# Pg1_Microcontroller.net
KiCad netlist of a schematic drawn in Altium Designer
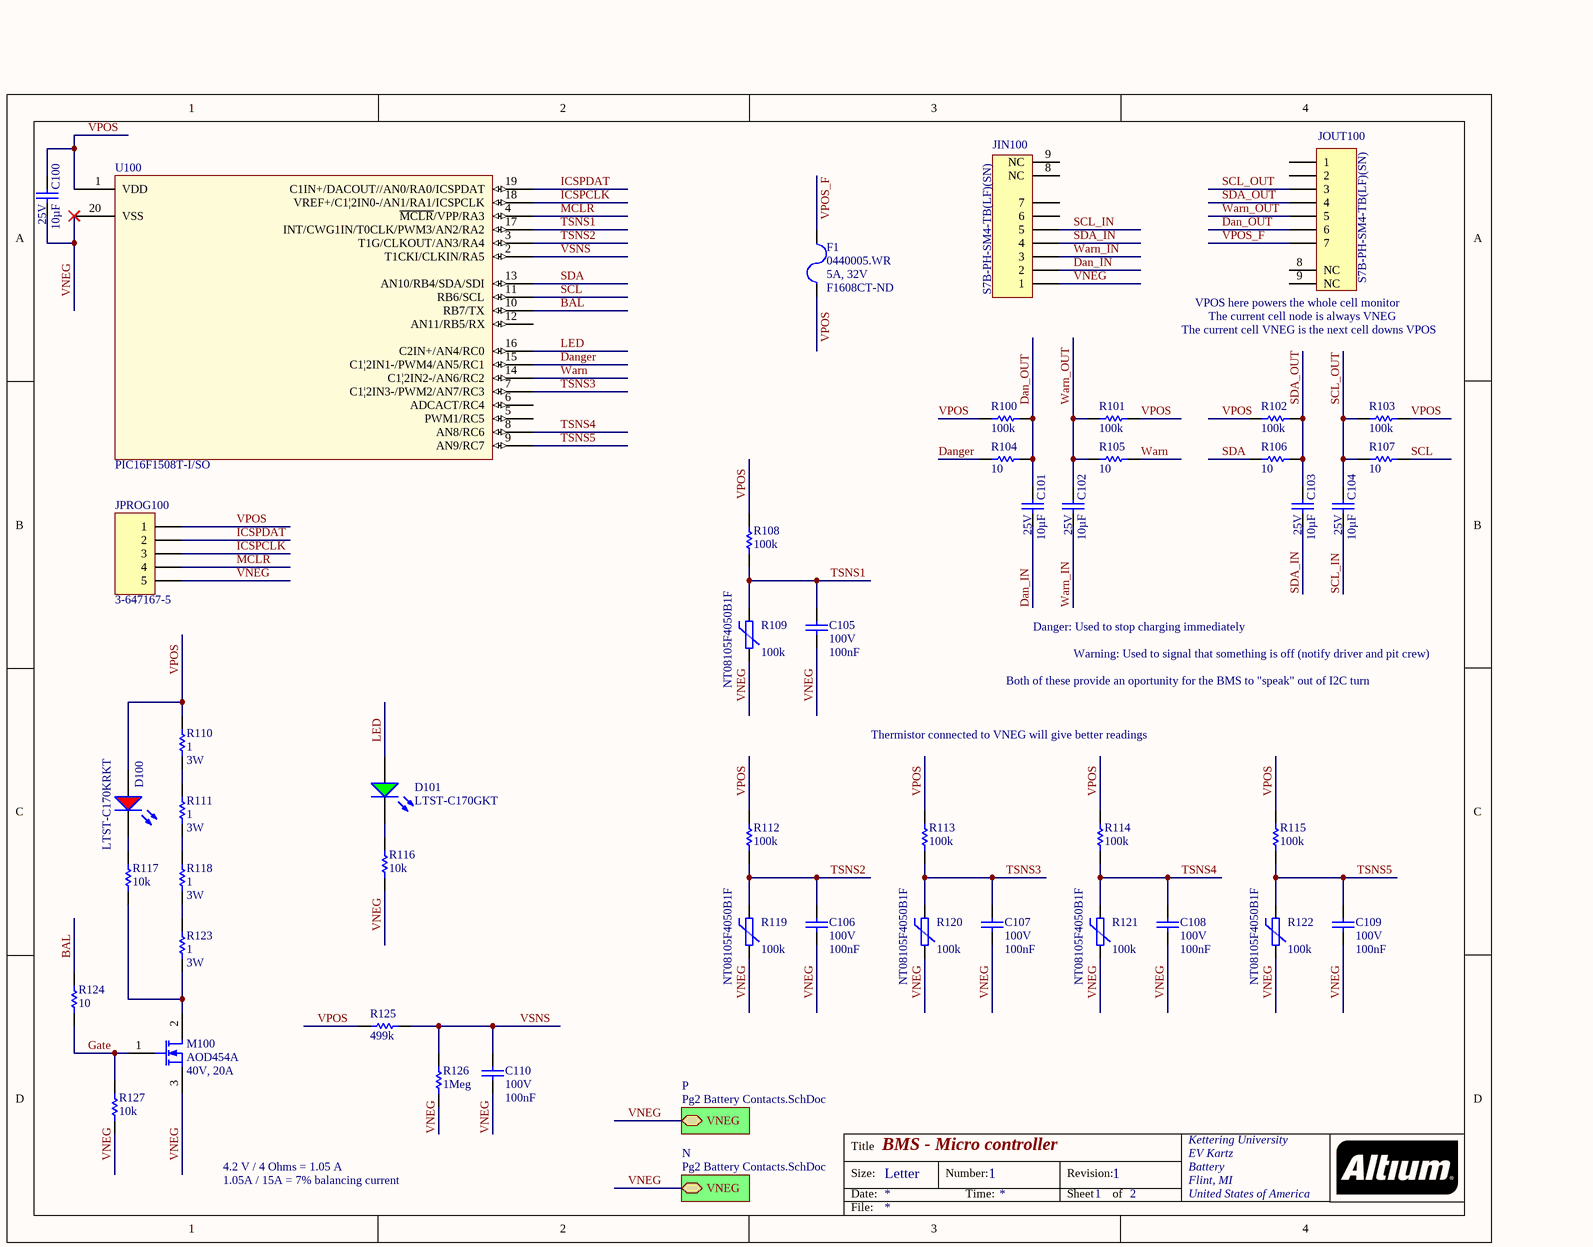
[diagram p0: Pg1 Microcontroller.SchDoc]

(export (version "E")
  (design (tool "Eeschema 10.0.6"))
  (components
    (comp (ref "C100")
      (value "10µF")
      (footprint "CAPC3225N")
      (description "Capacitor, Ceramic, 10µF, 25V, 0805, 10%, 125C")
      (fields (field (name "RATED") "25V") (field (name "Comment") "C1210C106K3RACAUTO"))
      (libsource (lib "SchLib - EE391 Master") (part "C1210C106K3RACAUTO"))
    )
    (comp (ref "C101")
      (value "10µF")
      (footprint "CAPC3225N")
      (description "Capacitor, Ceramic, 10µF, 25V, 0805, 10%, 125C")
      (fields (field (name "RATED") "25V") (field (name "Comment") "C1210C106K3RACAUTO"))
      (libsource (lib "SchLib - EE391 Master") (part "C1210C106K3RACAUTO"))
    )
    (comp (ref "C102")
      (value "10µF")
      (footprint "CAPC3225N")
      (description "Capacitor, Ceramic, 10µF, 25V, 0805, 10%, 125C")
      (fields (field (name "RATED") "25V") (field (name "Comment") "C1210C106K3RACAUTO"))
      (libsource (lib "SchLib - EE391 Master") (part "C1210C106K3RACAUTO"))
    )
    (comp (ref "C103")
      (value "10µF")
      (footprint "CAPC3225N")
      (description "Capacitor, Ceramic, 10µF, 25V, 0805, 10%, 125C")
      (fields (field (name "RATED") "25V") (field (name "Comment") "C1210C106K3RACAUTO"))
      (libsource (lib "SchLib - EE391 Master") (part "C1210C106K3RACAUTO"))
    )
    (comp (ref "C104")
      (value "10µF")
      (footprint "CAPC3225N")
      (description "Capacitor, Ceramic, 10µF, 25V, 0805, 10%, 125C")
      (fields (field (name "RATED") "25V") (field (name "Comment") "C1210C106K3RACAUTO"))
      (libsource (lib "SchLib - EE391 Master") (part "C1210C106K3RACAUTO"))
    )
    (comp (ref "C105")
      (value "100nF")
      (footprint "CAPC2012N")
      (description "Capacitor, Ceramic, 100nF, 100V, 0805, 10%, 125C")
      (fields (field (name "RATED") "100V") (field (name "Comment") "C0805C104K1RACAUTO"))
      (libsource (lib "SchLib - EE391 Master") (part "C0805C104K1RACAUTO"))
    )
    (comp (ref "C106")
      (value "100nF")
      (footprint "CAPC2012N")
      (description "Capacitor, Ceramic, 100nF, 100V, 0805, 10%, 125C")
      (fields (field (name "RATED") "100V") (field (name "Comment") "C0805C104K1RACAUTO"))
      (libsource (lib "SchLib - EE391 Master") (part "C0805C104K1RACAUTO"))
    )
    (comp (ref "C107")
      (value "100nF")
      (footprint "CAPC2012N")
      (description "Capacitor, Ceramic, 100nF, 100V, 0805, 10%, 125C")
      (fields (field (name "RATED") "100V") (field (name "Comment") "C0805C104K1RACAUTO"))
      (libsource (lib "SchLib - EE391 Master") (part "C0805C104K1RACAUTO"))
    )
    (comp (ref "C108")
      (value "100nF")
      (footprint "CAPC2012N")
      (description "Capacitor, Ceramic, 100nF, 100V, 0805, 10%, 125C")
      (fields (field (name "RATED") "100V") (field (name "Comment") "C0805C104K1RACAUTO"))
      (libsource (lib "SchLib - EE391 Master") (part "C0805C104K1RACAUTO"))
    )
    (comp (ref "C109")
      (value "100nF")
      (footprint "CAPC2012N")
      (description "Capacitor, Ceramic, 100nF, 100V, 0805, 10%, 125C")
      (fields (field (name "RATED") "100V") (field (name "Comment") "C0805C104K1RACAUTO"))
      (libsource (lib "SchLib - EE391 Master") (part "C0805C104K1RACAUTO"))
    )
    (comp (ref "C110")
      (value "100nF")
      (footprint "CAPC2012N")
      (description "Capacitor, Ceramic, 100nF, 100V, 0805, 10%, 125C")
      (fields (field (name "RATED") "100V") (field (name "Comment") "C0805C104K1RACAUTO"))
      (libsource (lib "SchLib - EE391 Master") (part "C0805C104K1RACAUTO"))
    )
    (comp (ref "D100")
      (value "LTST-C170KRKT")
      (footprint "DIO2012N-R")
      (description "LED, SMT 0805, Red, 2.0V, 20mA")
      (libsource (lib "SchLib - EE391 Master") (part "LTST-C170KRKT"))
    )
    (comp (ref "D101")
      (value "LTST-C170GKT")
      (footprint "DIO2012N-G")
      (description "LED, SMT 0805, Green, 2.1V, 10mA")
      (libsource (lib "SchLib - EE391 Master") (part "LTST-C170GKT"))
    )
    (comp (ref "F1")
      (value "0440005.WR")
      (footprint "CAPC1608N")
      (description "Fuse, SMT, 5A, 32VAC/VDC, 1206")
      (fields (field (name "RATED") "5A, 32V") (field (name "SUPPLIER PART NUMBER 1") "F1608CT-ND"))
      (libsource (lib "SchLib - EE391 Master") (part "0440005.WR"))
    )
    (comp (ref "JIN100")
      (value "S7B-PH-SM4-TB(LF)(SN)")
      (footprint "JST-PH-S7")
      (description "Header, JST, 7-Pin, Right-Angle, PH, Surface Mount")
      (libsource (lib "SchLib - EE391 Master") (part "S7B-PH-SM4-TB(LF)(SN)"))
    )
    (comp (ref "JOUT100")
      (value "S7B-PH-SM4-TB(LF)(SN)")
      (footprint "JST-PH-S7")
      (description "Header, JST, 7-Pin, Right-Angle, PH, Surface Mount")
      (libsource (lib "") (part "S7B-PH-SM4-TB(LF)(SN)_1"))
    )
    (comp (ref "JPROG100")
      (value "3-647167-5")
      (footprint "HDR1X5 SMT")
      (description "Header, 1x5-Pin, SMT, 100mil Pitch")
      (libsource (lib "SchLib - EE391 Master") (part "Hdr 3-647167-5"))
    )
    (comp (ref "M100")
      (value "AOD454A")
      (footprint "TO252-3N")
      (description "MOSFET, N-Ch, 40V, 20A, 430mOhm, TO252")
      (fields (field (name "RATED") "40V, 20A"))
      (libsource (lib "SchLib - EE391 Master") (part "AOD454A"))
    )
    (comp (ref "R100")
      (value "100k")
      (footprint "RESC2012N")
      (description "Resistor, Fixed, 100 kOhm, 0805, 1%, 1/8W")
      (fields (field (name "Comment") "ERJ-6ENF1003V"))
      (libsource (lib "SchLib - EE391 Master") (part "ERJ-6ENF1003V"))
    )
    (comp (ref "R101")
      (value "100k")
      (footprint "RESC2012N")
      (description "Resistor, Fixed, 100 kOhm, 0805, 1%, 1/8W")
      (fields (field (name "Comment") "ERJ-6ENF1003V"))
      (libsource (lib "SchLib - EE391 Master") (part "ERJ-6ENF1003V"))
    )
    (comp (ref "R102")
      (value "100k")
      (footprint "RESC2012N")
      (description "Resistor, Fixed, 100 kOhm, 0805, 1%, 1/8W")
      (fields (field (name "Comment") "ERJ-6ENF1003V"))
      (libsource (lib "SchLib - EE391 Master") (part "ERJ-6ENF1003V"))
    )
    (comp (ref "R103")
      (value "100k")
      (footprint "RESC2012N")
      (description "Resistor, Fixed, 100 kOhm, 0805, 1%, 1/8W")
      (fields (field (name "Comment") "ERJ-6ENF1003V"))
      (libsource (lib "SchLib - EE391 Master") (part "ERJ-6ENF1003V"))
    )
    (comp (ref "R104")
      (value "10")
      (footprint "RESC2012N")
      (description "Resistor, Fixed, 10 Ohm, 0805, 1%, 1/8W")
      (fields (field (name "Comment") "ERJ-6ENF10R0V"))
      (libsource (lib "SchLib - EE391 Master") (part "ERJ-6ENF10R0V"))
    )
    (comp (ref "R105")
      (value "10")
      (footprint "RESC2012N")
      (description "Resistor, Fixed, 10 Ohm, 0805, 1%, 1/8W")
      (fields (field (name "Comment") "ERJ-6ENF10R0V"))
      (libsource (lib "SchLib - EE391 Master") (part "ERJ-6ENF10R0V"))
    )
    (comp (ref "R106")
      (value "10")
      (footprint "RESC2012N")
      (description "Resistor, Fixed, 10 Ohm, 0805, 1%, 1/8W")
      (fields (field (name "Comment") "ERJ-6ENF10R0V"))
      (libsource (lib "SchLib - EE391 Master") (part "ERJ-6ENF10R0V"))
    )
    (comp (ref "R107")
      (value "10")
      (footprint "RESC2012N")
      (description "Resistor, Fixed, 10 Ohm, 0805, 1%, 1/8W")
      (fields (field (name "Comment") "ERJ-6ENF10R0V"))
      (libsource (lib "SchLib - EE391 Master") (part "ERJ-6ENF10R0V"))
    )
    (comp (ref "R108")
      (value "100k")
      (footprint "RESC2012N")
      (description "Resistor, Fixed, 100 kOhm, 0805, 1%, 1/8W")
      (fields (field (name "Comment") "ERJ-6ENF1003V"))
      (libsource (lib "SchLib - EE391 Master") (part "ERJ-6ENF1003V"))
    )
    (comp (ref "R109")
      (value "NT08105F4050B1F")
      (footprint "RESC2012N")
      (description "Resistor, NTC Thermistor, 100kOhm, 0805, 1%, 125C")
      (fields (field (name "ALTIUM_VALUE") "100k"))
      (libsource (lib "SchLib - EE391 Master") (part "NTCS0805E3103FMT"))
    )
    (comp (ref "R110")
      (value "1")
      (footprint "RESC6432N")
      (description "Resistor, Power, 1 Ohm, 6432, 5%, 3W")
      (fields (field (name "RATED") "3W") (field (name "Comment") "35221R0JT"))
      (libsource (lib "SchLib - EE391 Master") (part "35221R0JT"))
    )
    (comp (ref "R111")
      (value "1")
      (footprint "RESC6432N")
      (description "Resistor, Power, 1 Ohm, 6432, 5%, 3W")
      (fields (field (name "RATED") "3W") (field (name "Comment") "35221R0JT"))
      (libsource (lib "SchLib - EE391 Master") (part "35221R0JT"))
    )
    (comp (ref "R112")
      (value "100k")
      (footprint "RESC2012N")
      (description "Resistor, Fixed, 100 kOhm, 0805, 1%, 1/8W")
      (fields (field (name "Comment") "ERJ-6ENF1003V"))
      (libsource (lib "SchLib - EE391 Master") (part "ERJ-6ENF1003V"))
    )
    (comp (ref "R113")
      (value "100k")
      (footprint "RESC2012N")
      (description "Resistor, Fixed, 100 kOhm, 0805, 1%, 1/8W")
      (fields (field (name "Comment") "ERJ-6ENF1003V"))
      (libsource (lib "SchLib - EE391 Master") (part "ERJ-6ENF1003V"))
    )
    (comp (ref "R114")
      (value "100k")
      (footprint "RESC2012N")
      (description "Resistor, Fixed, 100 kOhm, 0805, 1%, 1/8W")
      (fields (field (name "Comment") "ERJ-6ENF1003V"))
      (libsource (lib "SchLib - EE391 Master") (part "ERJ-6ENF1003V"))
    )
    (comp (ref "R115")
      (value "100k")
      (footprint "RESC2012N")
      (description "Resistor, Fixed, 100 kOhm, 0805, 1%, 1/8W")
      (fields (field (name "Comment") "ERJ-6ENF1003V"))
      (libsource (lib "SchLib - EE391 Master") (part "ERJ-6ENF1003V"))
    )
    (comp (ref "R116")
      (value "10k")
      (footprint "RESC2012N")
      (description "Resistor, Fixed, 10 kOhm, 0805, 1%, 1/8W")
      (fields (field (name "Comment") "ERJ-6ENF1002V"))
      (libsource (lib "SchLib - EE391 Master") (part "ERJ-6ENF1002V"))
    )
    (comp (ref "R117")
      (value "10k")
      (footprint "RESC2012N")
      (description "Resistor, Fixed, 10 kOhm, 0805, 1%, 1/8W")
      (fields (field (name "Comment") "ERJ-6ENF1002V"))
      (libsource (lib "SchLib - EE391 Master") (part "ERJ-6ENF1002V"))
    )
    (comp (ref "R118")
      (value "1")
      (footprint "RESC6432N")
      (description "Resistor, Power, 1 Ohm, 6432, 5%, 3W")
      (fields (field (name "RATED") "3W") (field (name "Comment") "35221R0JT"))
      (libsource (lib "SchLib - EE391 Master") (part "35221R0JT"))
    )
    (comp (ref "R119")
      (value "NT08105F4050B1F")
      (footprint "RESC2012N")
      (description "Resistor, NTC Thermistor, 100kOhm, 0805, 1%, 125C")
      (fields (field (name "ALTIUM_VALUE") "100k"))
      (libsource (lib "SchLib - EE391 Master") (part "NTCS0805E3103FMT"))
    )
    (comp (ref "R120")
      (value "NT08105F4050B1F")
      (footprint "RESC2012N")
      (description "Resistor, NTC Thermistor, 100kOhm, 0805, 1%, 125C")
      (fields (field (name "ALTIUM_VALUE") "100k"))
      (libsource (lib "SchLib - EE391 Master") (part "NTCS0805E3103FMT"))
    )
    (comp (ref "R121")
      (value "NT08105F4050B1F")
      (footprint "RESC2012N")
      (description "Resistor, NTC Thermistor, 100kOhm, 0805, 1%, 125C")
      (fields (field (name "ALTIUM_VALUE") "100k"))
      (libsource (lib "SchLib - EE391 Master") (part "NTCS0805E3103FMT"))
    )
    (comp (ref "R122")
      (value "NT08105F4050B1F")
      (footprint "RESC2012N")
      (description "Resistor, NTC Thermistor, 100kOhm, 0805, 1%, 125C")
      (fields (field (name "ALTIUM_VALUE") "100k"))
      (libsource (lib "SchLib - EE391 Master") (part "NTCS0805E3103FMT"))
    )
    (comp (ref "R123")
      (value "1")
      (footprint "RESC6432N")
      (description "Resistor, Power, 1 Ohm, 6432, 5%, 3W")
      (fields (field (name "RATED") "3W") (field (name "Comment") "35221R0JT"))
      (libsource (lib "SchLib - EE391 Master") (part "35221R0JT"))
    )
    (comp (ref "R124")
      (value "10")
      (footprint "RESC2012N")
      (description "Resistor, Fixed, 10 Ohm, 0805, 1%, 1/8W")
      (fields (field (name "Comment") "ERJ-6ENF10R0V"))
      (libsource (lib "SchLib - EE391 Master") (part "ERJ-6ENF10R0V"))
    )
    (comp (ref "R125")
      (value "499k")
      (footprint "RESC2012N")
      (description "Resistor, Fixed, 499 kOhm, 0805, 1%, 1/8W")
      (fields (field (name "Comment") "ERJ-6ENF4993V"))
      (libsource (lib "SchLib - EE391 Master") (part "ERJ-6ENF4993V"))
    )
    (comp (ref "R126")
      (value "1Meg")
      (footprint "RESC2012N")
      (description "Resistor, Fixed, 1 MOhm, 0805, 1%, 1/8W")
      (fields (field (name "Comment") "ERJ-6ENF1004V"))
      (libsource (lib "SchLib - EE391 Master") (part "ERJ-6ENF1004V"))
    )
    (comp (ref "R127")
      (value "10k")
      (footprint "RESC2012N")
      (description "Resistor, Fixed, 10 kOhm, 0805, 1%, 1/8W")
      (fields (field (name "Comment") "ERJ-6ENF1002V"))
      (libsource (lib "SchLib - EE391 Master") (part "ERJ-6ENF1002V"))
    )
    (comp (ref "U100")
      (value "PIC16F1508T-I/SO")
      (footprint "SOIC-20-300")
      (description "MCU, 8-Bit, 5V, 32MHz, 20-Pin SOIC")
      (libsource (lib "SchLib - EE391 Master") (part "PIC16F1508T-I/SO"))
    )
  )
  (nets
    (net (code "1") (name "/BAL") (class "Default")
      (node (ref "R124") (pin "2") (pinfunction "2_2") (pintype "passive"))
      (node (ref "U100") (pin "10") (pinfunction "RB7/TX_10") (pintype "bidirectional"))
    )
    (net (code "2") (name "/Dan_IN") (class "Default")
      (node (ref "C101") (pin "1") (pinfunction "1_1") (pintype "passive"))
      (node (ref "JIN100") (pin "2") (pinfunction "2_2") (pintype "passive"))
    )
    (net (code "3") (name "/Dan_OUT") (class "Default")
      (node (ref "C101") (pin "2") (pinfunction "2_2") (pintype "passive"))
      (node (ref "JOUT100") (pin "6") (pinfunction "6_6") (pintype "passive"))
      (node (ref "R100") (pin "1") (pinfunction "1_1") (pintype "passive"))
      (node (ref "R104") (pin "2") (pinfunction "2_2") (pintype "passive"))
    )
    (net (code "4") (name "/Danger") (class "Default")
      (node (ref "R104") (pin "1") (pinfunction "1_1") (pintype "passive"))
      (node (ref "U100") (pin "15") (pinfunction "C1¦2IN1-/PWM4/AN5/RC1_15") (pintype "bidirectional"))
    )
    (net (code "5") (name "/Gate") (class "Default")
      (node (ref "M100") (pin "1") (pinfunction "G_1") (pintype "passive"))
      (node (ref "R124") (pin "1") (pinfunction "1_1") (pintype "passive"))
      (node (ref "R127") (pin "2") (pinfunction "2_2") (pintype "passive"))
    )
    (net (code "6") (name "/ICSPCLK") (class "Default")
      (node (ref "JPROG100") (pin "3") (pinfunction "3_3") (pintype "passive"))
      (node (ref "U100") (pin "18") (pinfunction "VREF+/C1¦2IN0-/AN1/RA1/ICSPCLK_18") (pintype "bidirectional"))
    )
    (net (code "7") (name "/ICSPDAT") (class "Default")
      (node (ref "JPROG100") (pin "2") (pinfunction "2_2") (pintype "passive"))
      (node (ref "U100") (pin "19") (pinfunction "C1IN+/DACOUT//AN0/RA0/ICSPDAT_19") (pintype "bidirectional"))
    )
    (net (code "8") (name "/LED") (class "Default")
      (node (ref "D101") (pin "1") (pinfunction "A_1") (pintype "passive"))
      (node (ref "U100") (pin "16") (pinfunction "C2IN+/AN4/RC0_16") (pintype "bidirectional"))
    )
    (net (code "9") (name "/MCLR") (class "Default")
      (node (ref "JPROG100") (pin "4") (pinfunction "4_4") (pintype "passive"))
      (node (ref "U100") (pin "4") (pinfunction "~{MCLR}/VPP/RA3_4") (pintype "bidirectional"))
    )
    (net (code "10") (name "/SCL") (class "Default")
      (node (ref "R107") (pin "2") (pinfunction "2_2") (pintype "passive"))
      (node (ref "U100") (pin "11") (pinfunction "RB6/SCL_11") (pintype "bidirectional"))
    )
    (net (code "11") (name "/SCL_IN") (class "Default")
      (node (ref "C104") (pin "1") (pinfunction "1_1") (pintype "passive"))
      (node (ref "JIN100") (pin "5") (pinfunction "5_5") (pintype "passive"))
    )
    (net (code "12") (name "/SCL_OUT") (class "Default")
      (node (ref "C104") (pin "2") (pinfunction "2_2") (pintype "passive"))
      (node (ref "JOUT100") (pin "3") (pinfunction "3_3") (pintype "passive"))
      (node (ref "R103") (pin "2") (pinfunction "2_2") (pintype "passive"))
      (node (ref "R107") (pin "1") (pinfunction "1_1") (pintype "passive"))
    )
    (net (code "13") (name "/SDA") (class "Default")
      (node (ref "R106") (pin "1") (pinfunction "1_1") (pintype "passive"))
      (node (ref "U100") (pin "13") (pinfunction "AN10/RB4/SDA/SDI_13") (pintype "bidirectional"))
    )
    (net (code "14") (name "/SDA_IN") (class "Default")
      (node (ref "C103") (pin "1") (pinfunction "1_1") (pintype "passive"))
      (node (ref "JIN100") (pin "4") (pinfunction "4_4") (pintype "passive"))
    )
    (net (code "15") (name "/SDA_OUT") (class "Default")
      (node (ref "C103") (pin "2") (pinfunction "2_2") (pintype "passive"))
      (node (ref "JOUT100") (pin "4") (pinfunction "4_4") (pintype "passive"))
      (node (ref "R102") (pin "1") (pinfunction "1_1") (pintype "passive"))
      (node (ref "R106") (pin "2") (pinfunction "2_2") (pintype "passive"))
    )
    (net (code "16") (name "/TSNS1") (class "Default")
      (node (ref "C105") (pin "1") (pinfunction "1_1") (pintype "passive"))
      (node (ref "R108") (pin "1") (pinfunction "1_1") (pintype "passive"))
      (node (ref "R109") (pin "1") (pinfunction "1_1") (pintype "passive"))
      (node (ref "U100") (pin "17") (pinfunction "INT/CWG1IN/T0CLK/PWM3/AN2/RA2_17") (pintype "bidirectional"))
    )
    (net (code "17") (name "/TSNS2") (class "Default")
      (node (ref "C106") (pin "1") (pinfunction "1_1") (pintype "passive"))
      (node (ref "R112") (pin "1") (pinfunction "1_1") (pintype "passive"))
      (node (ref "R119") (pin "1") (pinfunction "1_1") (pintype "passive"))
      (node (ref "U100") (pin "3") (pinfunction "T1G/CLKOUT/AN3/RA4_3") (pintype "bidirectional"))
    )
    (net (code "18") (name "/TSNS3") (class "Default")
      (node (ref "C107") (pin "1") (pinfunction "1_1") (pintype "passive"))
      (node (ref "R113") (pin "1") (pinfunction "1_1") (pintype "passive"))
      (node (ref "R120") (pin "1") (pinfunction "1_1") (pintype "passive"))
      (node (ref "U100") (pin "7") (pinfunction "C1¦2IN3-/PWM2/AN7/RC3_7") (pintype "bidirectional"))
    )
    (net (code "19") (name "/TSNS4") (class "Default")
      (node (ref "C108") (pin "1") (pinfunction "1_1") (pintype "passive"))
      (node (ref "R114") (pin "1") (pinfunction "1_1") (pintype "passive"))
      (node (ref "R121") (pin "1") (pinfunction "1_1") (pintype "passive"))
      (node (ref "U100") (pin "8") (pinfunction "AN8/RC6_8") (pintype "bidirectional"))
    )
    (net (code "20") (name "/TSNS5") (class "Default")
      (node (ref "C109") (pin "1") (pinfunction "1_1") (pintype "passive"))
      (node (ref "R115") (pin "1") (pinfunction "1_1") (pintype "passive"))
      (node (ref "R122") (pin "1") (pinfunction "1_1") (pintype "passive"))
      (node (ref "U100") (pin "9") (pinfunction "AN9/RC7_9") (pintype "bidirectional"))
    )
    (net (code "21") (name "/VNEG") (class "Default")
      (node (ref "C100") (pin "1") (pinfunction "1_1") (pintype "passive"))
      (node (ref "C105") (pin "2") (pinfunction "2_2") (pintype "passive"))
      (node (ref "C106") (pin "2") (pinfunction "2_2") (pintype "passive"))
      (node (ref "C107") (pin "2") (pinfunction "2_2") (pintype "passive"))
      (node (ref "C108") (pin "2") (pinfunction "2_2") (pintype "passive"))
      (node (ref "C109") (pin "2") (pinfunction "2_2") (pintype "passive"))
      (node (ref "C110") (pin "2") (pinfunction "2_2") (pintype "passive"))
      (node (ref "JIN100") (pin "1") (pinfunction "1_1") (pintype "passive"))
      (node (ref "JPROG100") (pin "5") (pinfunction "5_5") (pintype "passive"))
      (node (ref "M100") (pin "3") (pinfunction "S_3") (pintype "passive"))
      (node (ref "R109") (pin "2") (pinfunction "2_2") (pintype "passive"))
      (node (ref "R116") (pin "1") (pinfunction "1_1") (pintype "passive"))
      (node (ref "R119") (pin "2") (pinfunction "2_2") (pintype "passive"))
      (node (ref "R120") (pin "2") (pinfunction "2_2") (pintype "passive"))
      (node (ref "R121") (pin "2") (pinfunction "2_2") (pintype "passive"))
      (node (ref "R122") (pin "2") (pinfunction "2_2") (pintype "passive"))
      (node (ref "R126") (pin "1") (pinfunction "1_1") (pintype "passive"))
      (node (ref "R127") (pin "1") (pinfunction "1_1") (pintype "passive"))
      (node (ref "U100") (pin "20") (pinfunction "VSS_20") (pintype "power_in"))
    )
    (net (code "22") (name "/VPOS") (class "Default")
      (node (ref "C100") (pin "2") (pinfunction "2_2") (pintype "passive"))
      (node (ref "D100") (pin "1") (pinfunction "A_1") (pintype "passive"))
      (node (ref "F1") (pin "2") (pinfunction "2_2") (pintype "passive"))
      (node (ref "JPROG100") (pin "1") (pinfunction "1_1") (pintype "passive"))
      (node (ref "R100") (pin "2") (pinfunction "2_2") (pintype "passive"))
      (node (ref "R101") (pin "1") (pinfunction "1_1") (pintype "passive"))
      (node (ref "R102") (pin "2") (pinfunction "2_2") (pintype "passive"))
      (node (ref "R103") (pin "1") (pinfunction "1_1") (pintype "passive"))
      (node (ref "R108") (pin "2") (pinfunction "2_2") (pintype "passive"))
      (node (ref "R110") (pin "2") (pinfunction "2_2") (pintype "passive"))
      (node (ref "R112") (pin "2") (pinfunction "2_2") (pintype "passive"))
      (node (ref "R113") (pin "2") (pinfunction "2_2") (pintype "passive"))
      (node (ref "R114") (pin "2") (pinfunction "2_2") (pintype "passive"))
      (node (ref "R115") (pin "2") (pinfunction "2_2") (pintype "passive"))
      (node (ref "R125") (pin "2") (pinfunction "2_2") (pintype "passive"))
      (node (ref "U100") (pin "1") (pinfunction "VDD_1") (pintype "power_in"))
    )
    (net (code "23") (name "/VPOS_F") (class "Default")
      (node (ref "F1") (pin "1") (pinfunction "1_1") (pintype "passive"))
      (node (ref "JOUT100") (pin "7") (pinfunction "7_7") (pintype "passive"))
    )
    (net (code "24") (name "/VSNS") (class "Default")
      (node (ref "C110") (pin "1") (pinfunction "1_1") (pintype "passive"))
      (node (ref "R125") (pin "1") (pinfunction "1_1") (pintype "passive"))
      (node (ref "R126") (pin "2") (pinfunction "2_2") (pintype "passive"))
      (node (ref "U100") (pin "2") (pinfunction "T1CKI/CLKIN/RA5_2") (pintype "bidirectional"))
    )
    (net (code "25") (name "/Warn") (class "Default")
      (node (ref "R105") (pin "2") (pinfunction "2_2") (pintype "passive"))
      (node (ref "U100") (pin "14") (pinfunction "C1¦2IN2-/AN6/RC2_14") (pintype "bidirectional"))
    )
    (net (code "26") (name "/Warn_IN") (class "Default")
      (node (ref "C102") (pin "1") (pinfunction "1_1") (pintype "passive"))
      (node (ref "JIN100") (pin "3") (pinfunction "3_3") (pintype "passive"))
    )
    (net (code "27") (name "/Warn_OUT") (class "Default")
      (node (ref "C102") (pin "2") (pinfunction "2_2") (pintype "passive"))
      (node (ref "JOUT100") (pin "5") (pinfunction "5_5") (pintype "passive"))
      (node (ref "R101") (pin "2") (pinfunction "2_2") (pintype "passive"))
      (node (ref "R105") (pin "1") (pinfunction "1_1") (pintype "passive"))
    )
    (net (code "28") (name "Net-(D100-K)") (class "Default")
      (node (ref "D100") (pin "2") (pinfunction "K_2") (pintype "passive"))
      (node (ref "R117") (pin "2") (pinfunction "2_2") (pintype "passive"))
    )
    (net (code "29") (name "Net-(D101-K)") (class "Default")
      (node (ref "D101") (pin "2") (pinfunction "K_2") (pintype "passive"))
      (node (ref "R116") (pin "2") (pinfunction "2_2") (pintype "passive"))
    )
    (net (code "30") (name "Net-(M100-D)") (class "Default")
      (node (ref "M100") (pin "2") (pinfunction "D_2") (pintype "passive"))
      (node (ref "R117") (pin "1") (pinfunction "1_1") (pintype "passive"))
      (node (ref "R123") (pin "1") (pinfunction "1_1") (pintype "passive"))
    )
    (net (code "31") (name "Net-(R110-Pad1)") (class "Default")
      (node (ref "R110") (pin "1") (pinfunction "1_1") (pintype "passive"))
      (node (ref "R111") (pin "2") (pinfunction "2_2") (pintype "passive"))
    )
    (net (code "32") (name "Net-(R111-Pad1)") (class "Default")
      (node (ref "R111") (pin "1") (pinfunction "1_1") (pintype "passive"))
      (node (ref "R118") (pin "2") (pinfunction "2_2") (pintype "passive"))
    )
    (net (code "33") (name "Net-(R118-Pad1)") (class "Default")
      (node (ref "R118") (pin "1") (pinfunction "1_1") (pintype "passive"))
      (node (ref "R123") (pin "2") (pinfunction "2_2") (pintype "passive"))
    )
    (net (code "34") (name "unconnected-(JIN100-NC-Pad8)") (class "Default")
      (node (ref "JIN100") (pin "8") (pinfunction "NC_8") (pintype "tri_state"))
    )
    (net (code "35") (name "unconnected-(JIN100-NC-Pad9)") (class "Default")
      (node (ref "JIN100") (pin "9") (pinfunction "NC_9") (pintype "tri_state"))
    )
    (net (code "36") (name "unconnected-(JIN100-Pad6)") (class "Default")
      (node (ref "JIN100") (pin "6") (pinfunction "6_6") (pintype "passive"))
    )
    (net (code "37") (name "unconnected-(JIN100-Pad7)") (class "Default")
      (node (ref "JIN100") (pin "7") (pinfunction "7_7") (pintype "passive"))
    )
    (net (code "38") (name "unconnected-(JOUT100-NC-Pad8)") (class "Default")
      (node (ref "JOUT100") (pin "8") (pinfunction "NC_8") (pintype "tri_state"))
    )
    (net (code "39") (name "unconnected-(JOUT100-NC-Pad9)") (class "Default")
      (node (ref "JOUT100") (pin "9") (pinfunction "NC_9") (pintype "tri_state"))
    )
    (net (code "40") (name "unconnected-(JOUT100-Pad1)") (class "Default")
      (node (ref "JOUT100") (pin "1") (pinfunction "1_1") (pintype "passive"))
    )
    (net (code "41") (name "unconnected-(JOUT100-Pad2)") (class "Default")
      (node (ref "JOUT100") (pin "2") (pinfunction "2_2") (pintype "passive"))
    )
    (net (code "42") (name "unconnected-(U100-ADCACT{slash}RC4-Pad6)") (class "Default")
      (node (ref "U100") (pin "6") (pinfunction "ADCACT/RC4_6") (pintype "bidirectional"))
    )
    (net (code "43") (name "unconnected-(U100-AN11{slash}RB5{slash}RX-Pad12)") (class "Default")
      (node (ref "U100") (pin "12") (pinfunction "AN11/RB5/RX_12") (pintype "bidirectional"))
    )
    (net (code "44") (name "unconnected-(U100-PWM1{slash}RC5-Pad5)") (class "Default")
      (node (ref "U100") (pin "5") (pinfunction "PWM1/RC5_5") (pintype "bidirectional"))
    )
  )
)
